# Sheet2.net
KiCad netlist of a schematic drawn in Altium Designer
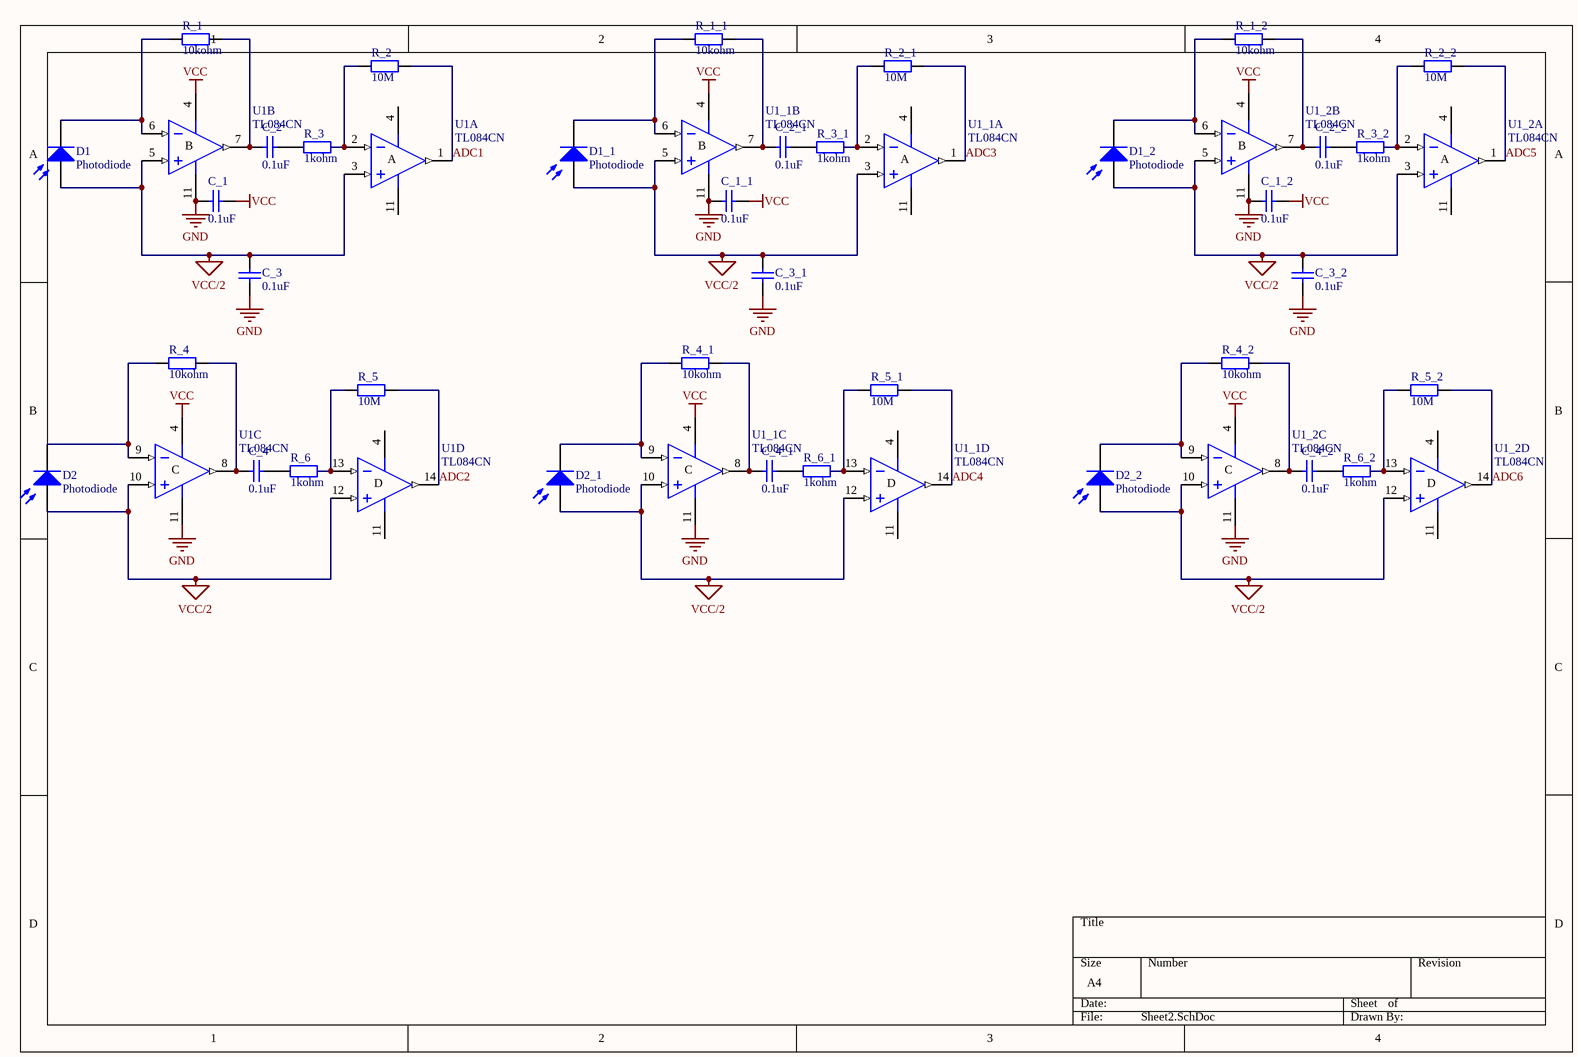
[diagram p0: Sheet2.SchDoc]

(export (version "E")
  (design (tool "Eeschema 10.0.6"))
  (components
    (comp (ref "C_1")
      (value "0.1uF")
      (footprint "cms805 - mini")
      (libsource (lib "lib_Robotronik") (part "Capa"))
    )
    (comp (ref "C_1_1")
      (value "0.1uF")
      (footprint "cms805 - mini")
      (libsource (lib "lib_Robotronik") (part "Capa"))
    )
    (comp (ref "C_1_2")
      (value "0.1uF")
      (footprint "cms805 - mini")
      (libsource (lib "lib_Robotronik") (part "Capa"))
    )
    (comp (ref "C_2")
      (value "0.1uF")
      (footprint "cms805 - mini")
      (libsource (lib "lib_Robotronik") (part "Capa"))
    )
    (comp (ref "C_2_1")
      (value "0.1uF")
      (footprint "cms805 - mini")
      (libsource (lib "lib_Robotronik") (part "Capa"))
    )
    (comp (ref "C_2_2")
      (value "0.1uF")
      (footprint "cms805 - mini")
      (libsource (lib "lib_Robotronik") (part "Capa"))
    )
    (comp (ref "C_3")
      (value "0.1uF")
      (footprint "cms805 - mini")
      (libsource (lib "lib_Robotronik") (part "Capa"))
    )
    (comp (ref "C_3_1")
      (value "0.1uF")
      (footprint "cms805 - mini")
      (libsource (lib "lib_Robotronik") (part "Capa"))
    )
    (comp (ref "C_3_2")
      (value "0.1uF")
      (footprint "cms805 - mini")
      (libsource (lib "lib_Robotronik") (part "Capa"))
    )
    (comp (ref "C_4")
      (value "0.1uF")
      (footprint "cms805 - mini")
      (libsource (lib "lib_Robotronik") (part "Capa"))
    )
    (comp (ref "C_4_1")
      (value "0.1uF")
      (footprint "cms805 - mini")
      (libsource (lib "lib_Robotronik") (part "Capa"))
    )
    (comp (ref "C_4_2")
      (value "0.1uF")
      (footprint "cms805 - mini")
      (libsource (lib "lib_Robotronik") (part "Capa"))
    )
    (comp (ref "D1")
      (value "Photodiode")
      (footprint "TEMD1000")
      (fields (field (name "PUBLISHER") "Altium Limited"))
      (libsource (lib "lib_Robotronik") (part "Photodiode"))
    )
    (comp (ref "D1_1")
      (value "Photodiode")
      (footprint "TEMD1000")
      (fields (field (name "PUBLISHER") "Altium Limited"))
      (libsource (lib "lib_Robotronik") (part "Photodiode"))
    )
    (comp (ref "D1_2")
      (value "Photodiode")
      (footprint "TEMD1000")
      (fields (field (name "PUBLISHER") "Altium Limited"))
      (libsource (lib "lib_Robotronik") (part "Photodiode"))
    )
    (comp (ref "D2")
      (value "Photodiode")
      (footprint "TEMD1000")
      (fields (field (name "PUBLISHER") "Altium Limited"))
      (libsource (lib "lib_Robotronik") (part "Photodiode"))
    )
    (comp (ref "D2_1")
      (value "Photodiode")
      (footprint "TEMD1000")
      (fields (field (name "PUBLISHER") "Altium Limited"))
      (libsource (lib "lib_Robotronik") (part "Photodiode"))
    )
    (comp (ref "D2_2")
      (value "Photodiode")
      (footprint "TEMD1000")
      (fields (field (name "PUBLISHER") "Altium Limited"))
      (libsource (lib "lib_Robotronik") (part "Photodiode"))
    )
    (comp (ref "R_1")
      (value "10kohm")
      (footprint "cms805 - mini")
      (libsource (lib "lib_Robotronik") (part "Resistance"))
    )
    (comp (ref "R_1_1")
      (value "10kohm")
      (footprint "cms805 - mini")
      (libsource (lib "lib_Robotronik") (part "Resistance"))
    )
    (comp (ref "R_1_2")
      (value "10kohm")
      (footprint "cms805 - mini")
      (libsource (lib "lib_Robotronik") (part "Resistance"))
    )
    (comp (ref "R_2")
      (value "10M")
      (footprint "cms805 - mini")
      (libsource (lib "lib_Robotronik") (part "Resistance"))
    )
    (comp (ref "R_2_1")
      (value "10M")
      (footprint "cms805 - mini")
      (libsource (lib "lib_Robotronik") (part "Resistance"))
    )
    (comp (ref "R_2_2")
      (value "10M")
      (footprint "cms805 - mini")
      (libsource (lib "lib_Robotronik") (part "Resistance"))
    )
    (comp (ref "R_3")
      (value "1kohm")
      (footprint "cms805 - mini")
      (libsource (lib "lib_Robotronik") (part "Resistance"))
    )
    (comp (ref "R_3_1")
      (value "1kohm")
      (footprint "cms805 - mini")
      (libsource (lib "lib_Robotronik") (part "Resistance"))
    )
    (comp (ref "R_3_2")
      (value "1kohm")
      (footprint "cms805 - mini")
      (libsource (lib "lib_Robotronik") (part "Resistance"))
    )
    (comp (ref "R_4")
      (value "10kohm")
      (footprint "cms805 - mini")
      (libsource (lib "lib_Robotronik") (part "Resistance"))
    )
    (comp (ref "R_4_1")
      (value "10kohm")
      (footprint "cms805 - mini")
      (libsource (lib "lib_Robotronik") (part "Resistance"))
    )
    (comp (ref "R_4_2")
      (value "10kohm")
      (footprint "cms805 - mini")
      (libsource (lib "lib_Robotronik") (part "Resistance"))
    )
    (comp (ref "R_5")
      (value "10M")
      (footprint "cms805 - mini")
      (libsource (lib "lib_Robotronik") (part "Resistance"))
    )
    (comp (ref "R_5_1")
      (value "10M")
      (footprint "cms805 - mini")
      (libsource (lib "lib_Robotronik") (part "Resistance"))
    )
    (comp (ref "R_5_2")
      (value "10M")
      (footprint "cms805 - mini")
      (libsource (lib "lib_Robotronik") (part "Resistance"))
    )
    (comp (ref "R_6")
      (value "1kohm")
      (footprint "cms805 - mini")
      (libsource (lib "lib_Robotronik") (part "Resistance"))
    )
    (comp (ref "R_6_1")
      (value "1kohm")
      (footprint "cms805 - mini")
      (libsource (lib "lib_Robotronik") (part "Resistance"))
    )
    (comp (ref "R_6_2")
      (value "1kohm")
      (footprint "cms805 - mini")
      (libsource (lib "lib_Robotronik") (part "Resistance"))
    )
    (comp (ref "U1")
      (value "TL084CN")
      (footprint "TSSOP14")
      (description "General-Purpose J-FET Quad Operational Amplifier")
      (fields (field (name "PUBLISHER") "Altium Limited"))
      (libsource (lib "lib_Robotronik") (part "TL084CN"))
    )
    (comp (ref "U1_1")
      (value "TL084CN")
      (footprint "TSSOP14")
      (description "General-Purpose J-FET Quad Operational Amplifier")
      (fields (field (name "PUBLISHER") "Altium Limited"))
      (libsource (lib "lib_Robotronik") (part "TL084CN"))
    )
    (comp (ref "U1_2")
      (value "TL084CN")
      (footprint "TSSOP14")
      (description "General-Purpose J-FET Quad Operational Amplifier")
      (fields (field (name "PUBLISHER") "Altium Limited"))
      (libsource (lib "lib_Robotronik") (part "TL084CN"))
    )
  )
  (nets
    (net (code "1") (name "/ADC1") (class "Default")
      (node (ref "R_2") (pin "2") (pinfunction "2_2") (pintype "passive"))
      (node (ref "U1") (pin "1") (pinfunction "OUT_1") (pintype "output"))
    )
    (net (code "2") (name "/ADC2") (class "Default")
      (node (ref "R_5") (pin "2") (pinfunction "2_2") (pintype "passive"))
      (node (ref "U1") (pin "14") (pinfunction "OUT_14") (pintype "output"))
    )
    (net (code "3") (name "/ADC3") (class "Default")
      (node (ref "R_2_1") (pin "2") (pinfunction "2_2") (pintype "passive"))
      (node (ref "U1_1") (pin "1") (pinfunction "OUT_1") (pintype "output"))
    )
    (net (code "4") (name "/ADC4") (class "Default")
      (node (ref "R_5_1") (pin "2") (pinfunction "2_2") (pintype "passive"))
      (node (ref "U1_1") (pin "14") (pinfunction "OUT_14") (pintype "output"))
    )
    (net (code "5") (name "/ADC5") (class "Default")
      (node (ref "R_2_2") (pin "2") (pinfunction "2_2") (pintype "passive"))
      (node (ref "U1_2") (pin "1") (pinfunction "OUT_1") (pintype "output"))
    )
    (net (code "6") (name "/ADC6") (class "Default")
      (node (ref "R_5_2") (pin "2") (pinfunction "2_2") (pintype "passive"))
      (node (ref "U1_2") (pin "14") (pinfunction "OUT_14") (pintype "output"))
    )
    (net (code "7") (name "GND") (class "Default")
      (node (ref "C_1") (pin "1") (pinfunction "1_1") (pintype "passive"))
      (node (ref "C_1_1") (pin "1") (pinfunction "1_1") (pintype "passive"))
      (node (ref "C_1_2") (pin "1") (pinfunction "1_1") (pintype "passive"))
      (node (ref "C_3") (pin "1") (pinfunction "1_1") (pintype "passive"))
      (node (ref "C_3_1") (pin "1") (pinfunction "1_1") (pintype "passive"))
      (node (ref "C_3_2") (pin "1") (pinfunction "1_1") (pintype "passive"))
      (node (ref "U1") (pin "11") (pinfunction "V-_11") (pintype "power_in"))
      (node (ref "U1_1") (pin "11") (pinfunction "V-_11") (pintype "power_in"))
      (node (ref "U1_2") (pin "11") (pinfunction "V-_11") (pintype "power_in"))
    )
    (net (code "8") (name "Net-(C_2-Pad1)") (class "Default")
      (node (ref "C_2") (pin "1") (pinfunction "1_1") (pintype "passive"))
      (node (ref "R_3") (pin "1") (pinfunction "1_1") (pintype "passive"))
    )
    (net (code "9") (name "Net-(C_2_1-Pad1)") (class "Default")
      (node (ref "C_2_1") (pin "1") (pinfunction "1_1") (pintype "passive"))
      (node (ref "R_3_1") (pin "1") (pinfunction "1_1") (pintype "passive"))
    )
    (net (code "10") (name "Net-(C_2_2-Pad1)") (class "Default")
      (node (ref "C_2_2") (pin "1") (pinfunction "1_1") (pintype "passive"))
      (node (ref "R_3_2") (pin "1") (pinfunction "1_1") (pintype "passive"))
    )
    (net (code "11") (name "Net-(C_4-Pad1)") (class "Default")
      (node (ref "C_4") (pin "1") (pinfunction "1_1") (pintype "passive"))
      (node (ref "R_6") (pin "1") (pinfunction "1_1") (pintype "passive"))
    )
    (net (code "12") (name "Net-(C_4_1-Pad1)") (class "Default")
      (node (ref "C_4_1") (pin "1") (pinfunction "1_1") (pintype "passive"))
      (node (ref "R_6_1") (pin "1") (pinfunction "1_1") (pintype "passive"))
    )
    (net (code "13") (name "Net-(C_4_2-Pad1)") (class "Default")
      (node (ref "C_4_2") (pin "1") (pinfunction "1_1") (pintype "passive"))
      (node (ref "R_6_2") (pin "1") (pinfunction "1_1") (pintype "passive"))
    )
    (net (code "14") (name "Net-(D1-K)") (class "Default")
      (node (ref "D1") (pin "2") (pinfunction "K_2") (pintype "passive"))
      (node (ref "R_1") (pin "1") (pinfunction "1_1") (pintype "passive"))
      (node (ref "U1") (pin "6") (pinfunction "IN-_6") (pintype "input"))
    )
    (net (code "15") (name "Net-(D1_1-K)") (class "Default")
      (node (ref "D1_1") (pin "2") (pinfunction "K_2") (pintype "passive"))
      (node (ref "R_1_1") (pin "1") (pinfunction "1_1") (pintype "passive"))
      (node (ref "U1_1") (pin "6") (pinfunction "IN-_6") (pintype "input"))
    )
    (net (code "16") (name "Net-(D1_2-K)") (class "Default")
      (node (ref "D1_2") (pin "2") (pinfunction "K_2") (pintype "passive"))
      (node (ref "R_1_2") (pin "1") (pinfunction "1_1") (pintype "passive"))
      (node (ref "U1_2") (pin "6") (pinfunction "IN-_6") (pintype "input"))
    )
    (net (code "17") (name "Net-(D2-K)") (class "Default")
      (node (ref "D2") (pin "2") (pinfunction "K_2") (pintype "passive"))
      (node (ref "R_4") (pin "1") (pinfunction "1_1") (pintype "passive"))
      (node (ref "U1") (pin "9") (pinfunction "IN-_9") (pintype "input"))
    )
    (net (code "18") (name "Net-(D2_1-K)") (class "Default")
      (node (ref "D2_1") (pin "2") (pinfunction "K_2") (pintype "passive"))
      (node (ref "R_4_1") (pin "1") (pinfunction "1_1") (pintype "passive"))
      (node (ref "U1_1") (pin "9") (pinfunction "IN-_9") (pintype "input"))
    )
    (net (code "19") (name "Net-(D2_2-K)") (class "Default")
      (node (ref "D2_2") (pin "2") (pinfunction "K_2") (pintype "passive"))
      (node (ref "R_4_2") (pin "1") (pinfunction "1_1") (pintype "passive"))
      (node (ref "U1_2") (pin "9") (pinfunction "IN-_9") (pintype "input"))
    )
    (net (code "20") (name "Net-(U1A-IN-)") (class "Default")
      (node (ref "R_2") (pin "1") (pinfunction "1_1") (pintype "passive"))
      (node (ref "R_3") (pin "2") (pinfunction "2_2") (pintype "passive"))
      (node (ref "U1") (pin "2") (pinfunction "IN-_2") (pintype "input"))
    )
    (net (code "21") (name "Net-(U1B-OUT)") (class "Default")
      (node (ref "C_2") (pin "2") (pinfunction "2_2") (pintype "passive"))
      (node (ref "R_1") (pin "2") (pinfunction "2_2") (pintype "passive"))
      (node (ref "U1") (pin "7") (pinfunction "OUT_7") (pintype "output"))
    )
    (net (code "22") (name "Net-(U1C-OUT)") (class "Default")
      (node (ref "C_4") (pin "2") (pinfunction "2_2") (pintype "passive"))
      (node (ref "R_4") (pin "2") (pinfunction "2_2") (pintype "passive"))
      (node (ref "U1") (pin "8") (pinfunction "OUT_8") (pintype "output"))
    )
    (net (code "23") (name "Net-(U1D-IN-)") (class "Default")
      (node (ref "R_5") (pin "1") (pinfunction "1_1") (pintype "passive"))
      (node (ref "R_6") (pin "2") (pinfunction "2_2") (pintype "passive"))
      (node (ref "U1") (pin "13") (pinfunction "IN-_13") (pintype "input"))
    )
    (net (code "24") (name "Net-(U1_1A-IN-)") (class "Default")
      (node (ref "R_2_1") (pin "1") (pinfunction "1_1") (pintype "passive"))
      (node (ref "R_3_1") (pin "2") (pinfunction "2_2") (pintype "passive"))
      (node (ref "U1_1") (pin "2") (pinfunction "IN-_2") (pintype "input"))
    )
    (net (code "25") (name "Net-(U1_1B-OUT)") (class "Default")
      (node (ref "C_2_1") (pin "2") (pinfunction "2_2") (pintype "passive"))
      (node (ref "R_1_1") (pin "2") (pinfunction "2_2") (pintype "passive"))
      (node (ref "U1_1") (pin "7") (pinfunction "OUT_7") (pintype "output"))
    )
    (net (code "26") (name "Net-(U1_1C-OUT)") (class "Default")
      (node (ref "C_4_1") (pin "2") (pinfunction "2_2") (pintype "passive"))
      (node (ref "R_4_1") (pin "2") (pinfunction "2_2") (pintype "passive"))
      (node (ref "U1_1") (pin "8") (pinfunction "OUT_8") (pintype "output"))
    )
    (net (code "27") (name "Net-(U1_1D-IN-)") (class "Default")
      (node (ref "R_5_1") (pin "1") (pinfunction "1_1") (pintype "passive"))
      (node (ref "R_6_1") (pin "2") (pinfunction "2_2") (pintype "passive"))
      (node (ref "U1_1") (pin "13") (pinfunction "IN-_13") (pintype "input"))
    )
    (net (code "28") (name "Net-(U1_2A-IN-)") (class "Default")
      (node (ref "R_2_2") (pin "1") (pinfunction "1_1") (pintype "passive"))
      (node (ref "R_3_2") (pin "2") (pinfunction "2_2") (pintype "passive"))
      (node (ref "U1_2") (pin "2") (pinfunction "IN-_2") (pintype "input"))
    )
    (net (code "29") (name "Net-(U1_2B-OUT)") (class "Default")
      (node (ref "C_2_2") (pin "2") (pinfunction "2_2") (pintype "passive"))
      (node (ref "R_1_2") (pin "2") (pinfunction "2_2") (pintype "passive"))
      (node (ref "U1_2") (pin "7") (pinfunction "OUT_7") (pintype "output"))
    )
    (net (code "30") (name "Net-(U1_2C-OUT)") (class "Default")
      (node (ref "C_4_2") (pin "2") (pinfunction "2_2") (pintype "passive"))
      (node (ref "R_4_2") (pin "2") (pinfunction "2_2") (pintype "passive"))
      (node (ref "U1_2") (pin "8") (pinfunction "OUT_8") (pintype "output"))
    )
    (net (code "31") (name "Net-(U1_2D-IN-)") (class "Default")
      (node (ref "R_5_2") (pin "1") (pinfunction "1_1") (pintype "passive"))
      (node (ref "R_6_2") (pin "2") (pinfunction "2_2") (pintype "passive"))
      (node (ref "U1_2") (pin "13") (pinfunction "IN-_13") (pintype "input"))
    )
    (net (code "32") (name "VCC") (class "Default")
      (node (ref "C_1") (pin "2") (pinfunction "2_2") (pintype "passive"))
      (node (ref "C_1_1") (pin "2") (pinfunction "2_2") (pintype "passive"))
      (node (ref "C_1_2") (pin "2") (pinfunction "2_2") (pintype "passive"))
      (node (ref "U1") (pin "4") (pinfunction "V+_4") (pintype "power_in"))
      (node (ref "U1_1") (pin "4") (pinfunction "V+_4") (pintype "power_in"))
      (node (ref "U1_2") (pin "4") (pinfunction "V+_4") (pintype "power_in"))
    )
    (net (code "33") (name "VCC{slash}2") (class "Default")
      (node (ref "C_3") (pin "2") (pinfunction "2_2") (pintype "passive"))
      (node (ref "C_3_1") (pin "2") (pinfunction "2_2") (pintype "passive"))
      (node (ref "C_3_2") (pin "2") (pinfunction "2_2") (pintype "passive"))
      (node (ref "D1") (pin "1") (pinfunction "A_1") (pintype "passive"))
      (node (ref "D1_1") (pin "1") (pinfunction "A_1") (pintype "passive"))
      (node (ref "D1_2") (pin "1") (pinfunction "A_1") (pintype "passive"))
      (node (ref "D2") (pin "1") (pinfunction "A_1") (pintype "passive"))
      (node (ref "D2_1") (pin "1") (pinfunction "A_1") (pintype "passive"))
      (node (ref "D2_2") (pin "1") (pinfunction "A_1") (pintype "passive"))
      (node (ref "U1") (pin "10") (pinfunction "IN+_10") (pintype "input"))
      (node (ref "U1") (pin "12") (pinfunction "IN+_12") (pintype "input"))
      (node (ref "U1") (pin "3") (pinfunction "IN+_3") (pintype "input"))
      (node (ref "U1") (pin "5") (pinfunction "IN+_5") (pintype "input"))
      (node (ref "U1_1") (pin "10") (pinfunction "IN+_10") (pintype "input"))
      (node (ref "U1_1") (pin "12") (pinfunction "IN+_12") (pintype "input"))
      (node (ref "U1_1") (pin "3") (pinfunction "IN+_3") (pintype "input"))
      (node (ref "U1_1") (pin "5") (pinfunction "IN+_5") (pintype "input"))
      (node (ref "U1_2") (pin "10") (pinfunction "IN+_10") (pintype "input"))
      (node (ref "U1_2") (pin "12") (pinfunction "IN+_12") (pintype "input"))
      (node (ref "U1_2") (pin "3") (pinfunction "IN+_3") (pintype "input"))
      (node (ref "U1_2") (pin "5") (pinfunction "IN+_5") (pintype "input"))
    )
    (net (code "34") (name "unconnected-(U1A-V+-Pad4)") (class "Default")
      (node (ref "U1") (pin "4") (pinfunction "V+_4") (pintype "power_in"))
    )
    (net (code "35") (name "unconnected-(U1A-V--Pad11)") (class "Default")
      (node (ref "U1") (pin "11") (pinfunction "V-_11") (pintype "power_in"))
    )
    (net (code "36") (name "unconnected-(U1D-V+-Pad4)") (class "Default")
      (node (ref "U1") (pin "4") (pinfunction "V+_4") (pintype "power_in"))
    )
    (net (code "37") (name "unconnected-(U1D-V--Pad11)") (class "Default")
      (node (ref "U1") (pin "11") (pinfunction "V-_11") (pintype "power_in"))
    )
    (net (code "38") (name "unconnected-(U1_1A-V+-Pad4)") (class "Default")
      (node (ref "U1_1") (pin "4") (pinfunction "V+_4") (pintype "power_in"))
    )
    (net (code "39") (name "unconnected-(U1_1A-V--Pad11)") (class "Default")
      (node (ref "U1_1") (pin "11") (pinfunction "V-_11") (pintype "power_in"))
    )
    (net (code "40") (name "unconnected-(U1_1D-V+-Pad4)") (class "Default")
      (node (ref "U1_1") (pin "4") (pinfunction "V+_4") (pintype "power_in"))
    )
    (net (code "41") (name "unconnected-(U1_1D-V--Pad11)") (class "Default")
      (node (ref "U1_1") (pin "11") (pinfunction "V-_11") (pintype "power_in"))
    )
    (net (code "42") (name "unconnected-(U1_2A-V+-Pad4)") (class "Default")
      (node (ref "U1_2") (pin "4") (pinfunction "V+_4") (pintype "power_in"))
    )
    (net (code "43") (name "unconnected-(U1_2A-V--Pad11)") (class "Default")
      (node (ref "U1_2") (pin "11") (pinfunction "V-_11") (pintype "power_in"))
    )
    (net (code "44") (name "unconnected-(U1_2D-V+-Pad4)") (class "Default")
      (node (ref "U1_2") (pin "4") (pinfunction "V+_4") (pintype "power_in"))
    )
    (net (code "45") (name "unconnected-(U1_2D-V--Pad11)") (class "Default")
      (node (ref "U1_2") (pin "11") (pinfunction "V-_11") (pintype "power_in"))
    )
  )
)
